# MotorDriverModule.net
KiCad netlist of a schematic drawn in EAGLE
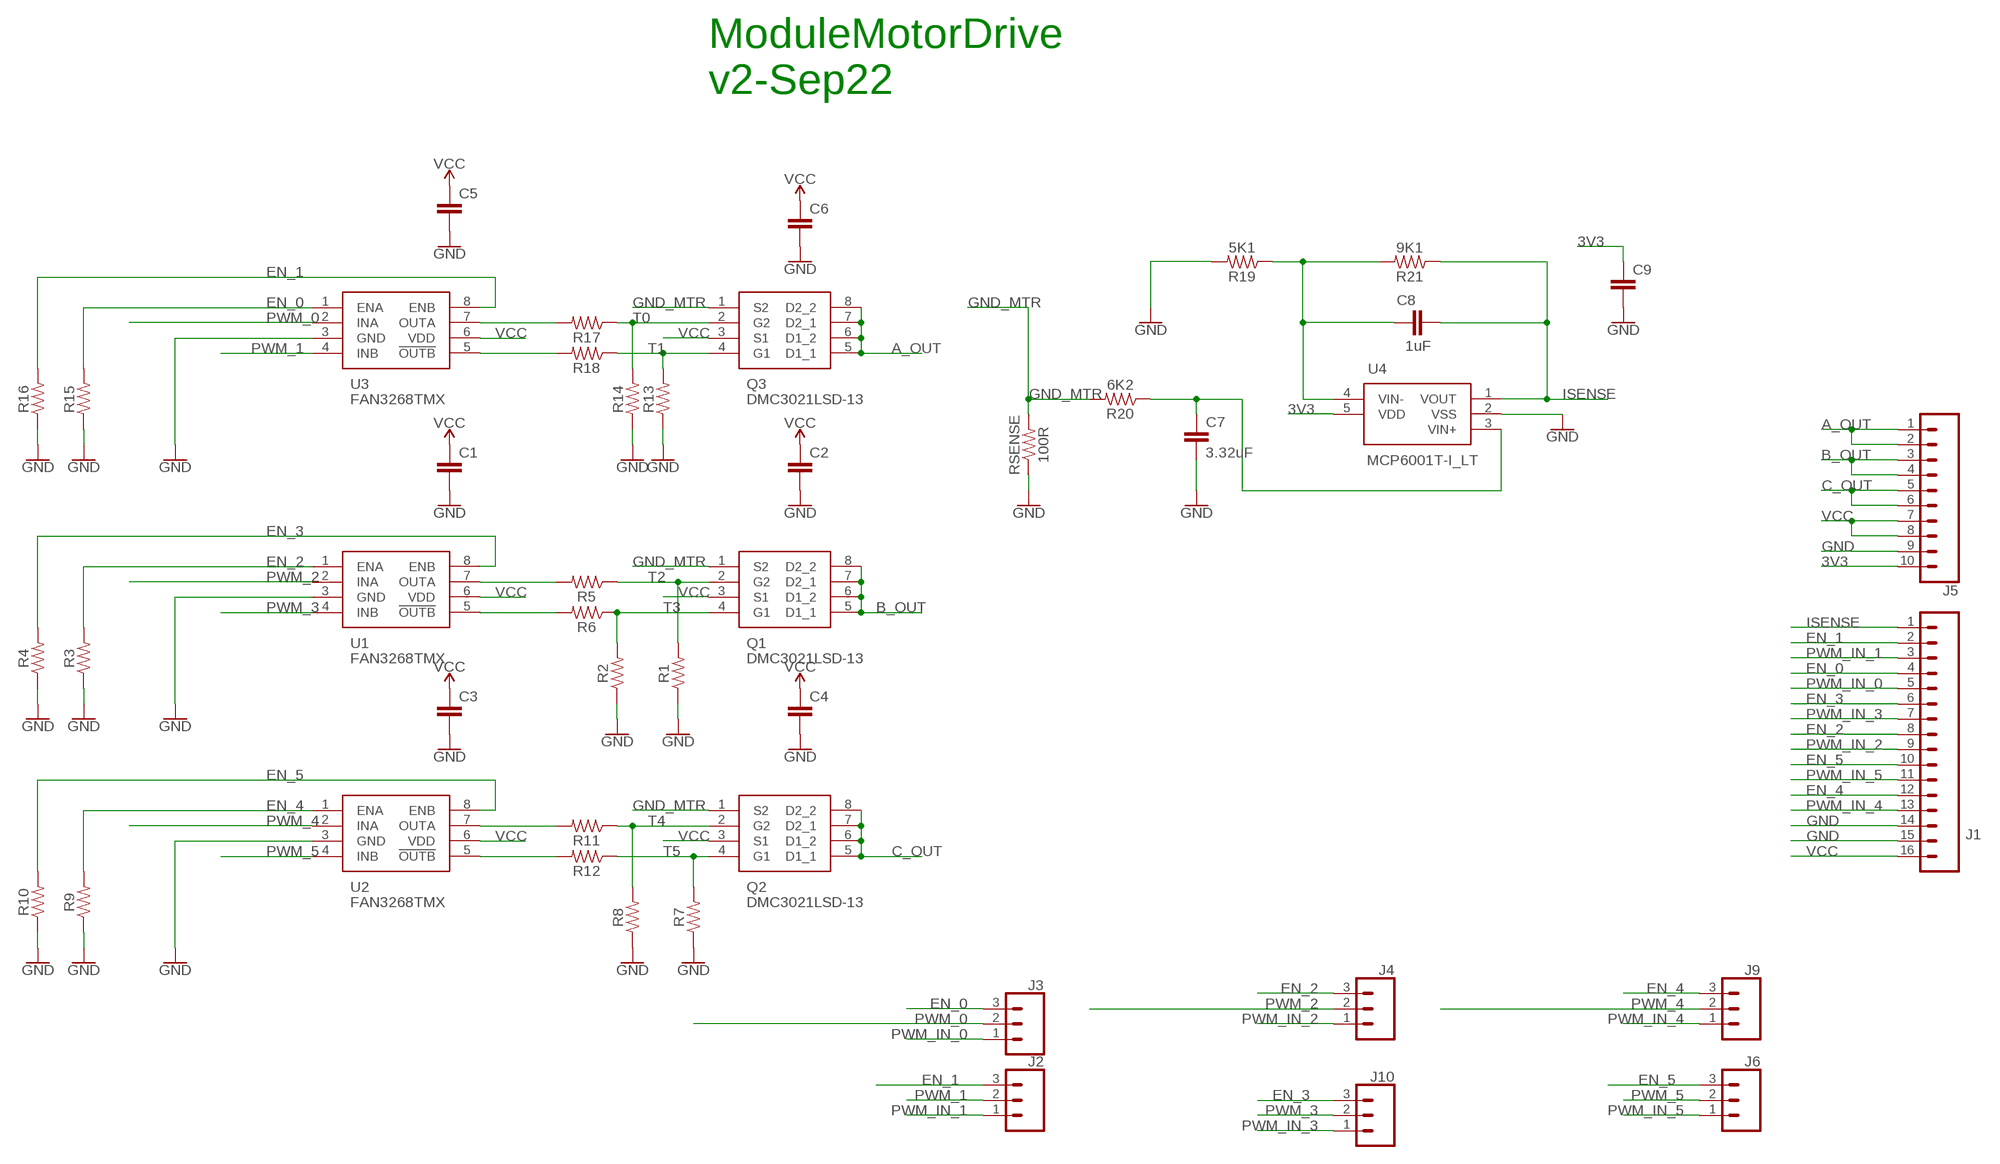
[diagram p0: schematic, sheet 1]

(export (version "E")
  (design (tool "Eeschema 10.0.6"))
  (components
    (comp (ref "C1")
      (value "C-EUC0805")
      (footprint "eagle-import:C0805")
      (libsource (lib "eagle-import") (part "C-EUC0805"))
    )
    (comp (ref "C2")
      (value "C-EUC0805")
      (footprint "eagle-import:C0805")
      (libsource (lib "eagle-import") (part "C-EUC0805"))
    )
    (comp (ref "C3")
      (value "C-EUC0805")
      (footprint "eagle-import:C0805")
      (libsource (lib "eagle-import") (part "C-EUC0805"))
    )
    (comp (ref "C4")
      (value "C-EUC0805")
      (footprint "eagle-import:C0805")
      (libsource (lib "eagle-import") (part "C-EUC0805"))
    )
    (comp (ref "C5")
      (value "C-EUC0805")
      (footprint "eagle-import:C0805")
      (libsource (lib "eagle-import") (part "C-EUC0805"))
    )
    (comp (ref "C6")
      (value "C-EUC0805")
      (footprint "eagle-import:C0805")
      (libsource (lib "eagle-import") (part "C-EUC0805"))
    )
    (comp (ref "C7")
      (value "3.32uF")
      (footprint "eagle-import:C0805")
      (libsource (lib "eagle-import") (part "C-EUC0805"))
    )
    (comp (ref "C8")
      (value "1uF")
      (footprint "eagle-import:C0805")
      (libsource (lib "eagle-import") (part "C-EUC0805"))
    )
    (comp (ref "C9")
      (value "C-EUC0805")
      (footprint "eagle-import:C0805")
      (libsource (lib "eagle-import") (part "C-EUC0805"))
    )
    (comp (ref "J1")
      (value "CONN_16")
      (footprint "eagle-import:1X16")
      (libsource (lib "eagle-import") (part "CONN_16"))
    )
    (comp (ref "J2")
      (value "CONN_03")
      (footprint "eagle-import:1X03")
      (libsource (lib "eagle-import") (part "CONN_03"))
    )
    (comp (ref "J3")
      (value "CONN_03")
      (footprint "eagle-import:1X03")
      (libsource (lib "eagle-import") (part "CONN_03"))
    )
    (comp (ref "J4")
      (value "CONN_03")
      (footprint "eagle-import:1X03")
      (libsource (lib "eagle-import") (part "CONN_03"))
    )
    (comp (ref "J5")
      (value "CONN_10\"")
      (footprint "eagle-import:1X10")
      (libsource (lib "eagle-import") (part "CONN_10{dblquote}"))
    )
    (comp (ref "J6")
      (value "CONN_03")
      (footprint "eagle-import:1X03")
      (libsource (lib "eagle-import") (part "CONN_03"))
    )
    (comp (ref "J9")
      (value "CONN_03")
      (footprint "eagle-import:1X03")
      (libsource (lib "eagle-import") (part "CONN_03"))
    )
    (comp (ref "J10")
      (value "CONN_03")
      (footprint "eagle-import:1X03")
      (libsource (lib "eagle-import") (part "CONN_03"))
    )
    (comp (ref "Q1")
      (value "DMC3021LSD-13")
      (footprint "eagle-import:SOIC127P600X175-8N")
      (fields (field (name "MOUSER_PART_NUMBER") "621-DMC3021LSD-13"))
      (libsource (lib "eagle-import") (part "DMC3021LSD-13"))
    )
    (comp (ref "Q2")
      (value "DMC3021LSD-13")
      (footprint "eagle-import:SOIC127P600X175-8N")
      (fields (field (name "MOUSER_PART_NUMBER") "621-DMC3021LSD-13"))
      (libsource (lib "eagle-import") (part "DMC3021LSD-13"))
    )
    (comp (ref "Q3")
      (value "DMC3021LSD-13")
      (footprint "eagle-import:SOIC127P600X175-8N")
      (fields (field (name "MOUSER_PART_NUMBER") "621-DMC3021LSD-13"))
      (libsource (lib "eagle-import") (part "DMC3021LSD-13"))
    )
    (comp (ref "R1")
      (value "RESISTOR0805")
      (footprint "eagle-import:0805")
      (libsource (lib "eagle-import") (part "RESISTOR0805"))
    )
    (comp (ref "R2")
      (value "RESISTOR0805")
      (footprint "eagle-import:0805")
      (libsource (lib "eagle-import") (part "RESISTOR0805"))
    )
    (comp (ref "R3")
      (value "RESISTOR0805")
      (footprint "eagle-import:0805")
      (libsource (lib "eagle-import") (part "RESISTOR0805"))
    )
    (comp (ref "R4")
      (value "RESISTOR0805")
      (footprint "eagle-import:0805")
      (libsource (lib "eagle-import") (part "RESISTOR0805"))
    )
    (comp (ref "R5")
      (value "RESISTOR0805")
      (footprint "eagle-import:0805")
      (libsource (lib "eagle-import") (part "RESISTOR0805"))
    )
    (comp (ref "R6")
      (value "RESISTOR0805")
      (footprint "eagle-import:0805")
      (libsource (lib "eagle-import") (part "RESISTOR0805"))
    )
    (comp (ref "R7")
      (value "RESISTOR0805")
      (footprint "eagle-import:0805")
      (libsource (lib "eagle-import") (part "RESISTOR0805"))
    )
    (comp (ref "R8")
      (value "RESISTOR0805")
      (footprint "eagle-import:0805")
      (libsource (lib "eagle-import") (part "RESISTOR0805"))
    )
    (comp (ref "R9")
      (value "RESISTOR0805")
      (footprint "eagle-import:0805")
      (libsource (lib "eagle-import") (part "RESISTOR0805"))
    )
    (comp (ref "R10")
      (value "RESISTOR0805")
      (footprint "eagle-import:0805")
      (libsource (lib "eagle-import") (part "RESISTOR0805"))
    )
    (comp (ref "R11")
      (value "RESISTOR0805")
      (footprint "eagle-import:0805")
      (libsource (lib "eagle-import") (part "RESISTOR0805"))
    )
    (comp (ref "R12")
      (value "RESISTOR0805")
      (footprint "eagle-import:0805")
      (libsource (lib "eagle-import") (part "RESISTOR0805"))
    )
    (comp (ref "R13")
      (value "RESISTOR0805")
      (footprint "eagle-import:0805")
      (libsource (lib "eagle-import") (part "RESISTOR0805"))
    )
    (comp (ref "R14")
      (value "RESISTOR0805")
      (footprint "eagle-import:0805")
      (libsource (lib "eagle-import") (part "RESISTOR0805"))
    )
    (comp (ref "R15")
      (value "RESISTOR0805")
      (footprint "eagle-import:0805")
      (libsource (lib "eagle-import") (part "RESISTOR0805"))
    )
    (comp (ref "R16")
      (value "RESISTOR0805")
      (footprint "eagle-import:0805")
      (libsource (lib "eagle-import") (part "RESISTOR0805"))
    )
    (comp (ref "R17")
      (value "RESISTOR0805")
      (footprint "eagle-import:0805")
      (libsource (lib "eagle-import") (part "RESISTOR0805"))
    )
    (comp (ref "R18")
      (value "RESISTOR0805")
      (footprint "eagle-import:0805")
      (libsource (lib "eagle-import") (part "RESISTOR0805"))
    )
    (comp (ref "R19")
      (value "5K1")
      (footprint "eagle-import:0805")
      (libsource (lib "eagle-import") (part "RESISTOR0805"))
    )
    (comp (ref "R20")
      (value "6K2")
      (footprint "eagle-import:0805")
      (libsource (lib "eagle-import") (part "RESISTOR0805"))
    )
    (comp (ref "R21")
      (value "9K1")
      (footprint "eagle-import:0805")
      (libsource (lib "eagle-import") (part "RESISTOR0805"))
    )
    (comp (ref "RSENSE")
      (value "100R")
      (footprint "eagle-import:1206")
      (libsource (lib "eagle-import") (part "RESISTOR1206"))
    )
    (comp (ref "U1")
      (value "FAN3268TMX")
      (footprint "eagle-import:SOIC127P600X175-8N")
      (fields (field (name "MOUSER_PART_NUMBER") "512-FAN3268TMX"))
      (libsource (lib "eagle-import") (part "FAN3268TMX"))
    )
    (comp (ref "U2")
      (value "FAN3268TMX")
      (footprint "eagle-import:SOIC127P600X175-8N")
      (fields (field (name "MOUSER_PART_NUMBER") "512-FAN3268TMX"))
      (libsource (lib "eagle-import") (part "FAN3268TMX"))
    )
    (comp (ref "U3")
      (value "FAN3268TMX")
      (footprint "eagle-import:SOIC127P600X175-8N")
      (fields (field (name "MOUSER_PART_NUMBER") "512-FAN3268TMX"))
      (libsource (lib "eagle-import") (part "FAN3268TMX"))
    )
    (comp (ref "U4")
      (value "MCP6001T-I_LT")
      (footprint "eagle-import:SOT65P210X110-5N")
      (fields
        (field (name "ARROW_PART_NUMBER") "MCP6001T-I/LT")
        (field (name "MOUSER_PART_NUMBER") "579-MCP6001T-I/LT")
      )
      (libsource (lib "eagle-import") (part "MCP6001T-I_LT"))
    )
  )
  (nets
    (net (code "1") (name "/3V3") (class "Default")
      (node (ref "C9") (pin "1") (pinfunction "1_1") (pintype "passive"))
      (node (ref "J5") (pin "10") (pinfunction "10_10") (pintype "passive"))
      (node (ref "U4") (pin "5") (pinfunction "VDD_5") (pintype "bidirectional"))
    )
    (net (code "2") (name "/A_OUT") (class "Default")
      (node (ref "J5") (pin "1") (pinfunction "1_1") (pintype "passive"))
      (node (ref "J5") (pin "2") (pinfunction "2_2") (pintype "passive"))
      (node (ref "Q3") (pin "5") (pinfunction "D1_1_5") (pintype "bidirectional"))
      (node (ref "Q3") (pin "6") (pinfunction "D1_2_6") (pintype "bidirectional"))
      (node (ref "Q3") (pin "7") (pinfunction "D2_1_7") (pintype "bidirectional"))
      (node (ref "Q3") (pin "8") (pinfunction "D2_2_8") (pintype "bidirectional"))
    )
    (net (code "3") (name "/B_OUT") (class "Default")
      (node (ref "J5") (pin "3") (pinfunction "3_3") (pintype "passive"))
      (node (ref "J5") (pin "4") (pinfunction "4_4") (pintype "passive"))
      (node (ref "Q1") (pin "5") (pinfunction "D1_1_5") (pintype "bidirectional"))
      (node (ref "Q1") (pin "6") (pinfunction "D1_2_6") (pintype "bidirectional"))
      (node (ref "Q1") (pin "7") (pinfunction "D2_1_7") (pintype "bidirectional"))
      (node (ref "Q1") (pin "8") (pinfunction "D2_2_8") (pintype "bidirectional"))
    )
    (net (code "4") (name "/C_OUT") (class "Default")
      (node (ref "J5") (pin "5") (pinfunction "5_5") (pintype "passive"))
      (node (ref "J5") (pin "6") (pinfunction "6_6") (pintype "passive"))
      (node (ref "Q2") (pin "5") (pinfunction "D1_1_5") (pintype "bidirectional"))
      (node (ref "Q2") (pin "6") (pinfunction "D1_2_6") (pintype "bidirectional"))
      (node (ref "Q2") (pin "7") (pinfunction "D2_1_7") (pintype "bidirectional"))
      (node (ref "Q2") (pin "8") (pinfunction "D2_2_8") (pintype "bidirectional"))
    )
    (net (code "5") (name "/EN_0") (class "Default")
      (node (ref "J1") (pin "4") (pinfunction "4_4") (pintype "passive"))
      (node (ref "J3") (pin "3") (pinfunction "3_3") (pintype "passive"))
      (node (ref "R15") (pin "2") (pinfunction "2_2") (pintype "passive"))
      (node (ref "U3") (pin "1") (pinfunction "ENA_1") (pintype "bidirectional"))
    )
    (net (code "6") (name "/EN_1") (class "Default")
      (node (ref "J1") (pin "2") (pinfunction "2_2") (pintype "passive"))
      (node (ref "J2") (pin "3") (pinfunction "3_3") (pintype "passive"))
      (node (ref "R16") (pin "2") (pinfunction "2_2") (pintype "passive"))
      (node (ref "U3") (pin "8") (pinfunction "ENB_8") (pintype "bidirectional"))
    )
    (net (code "7") (name "/EN_2") (class "Default")
      (node (ref "J1") (pin "8") (pinfunction "8_8") (pintype "passive"))
      (node (ref "J4") (pin "3") (pinfunction "3_3") (pintype "passive"))
      (node (ref "R3") (pin "2") (pinfunction "2_2") (pintype "passive"))
      (node (ref "U1") (pin "1") (pinfunction "ENA_1") (pintype "bidirectional"))
    )
    (net (code "8") (name "/EN_3") (class "Default")
      (node (ref "J1") (pin "6") (pinfunction "6_6") (pintype "passive"))
      (node (ref "J10") (pin "3") (pinfunction "3_3") (pintype "passive"))
      (node (ref "R4") (pin "2") (pinfunction "2_2") (pintype "passive"))
      (node (ref "U1") (pin "8") (pinfunction "ENB_8") (pintype "bidirectional"))
    )
    (net (code "9") (name "/EN_4") (class "Default")
      (node (ref "J1") (pin "12") (pinfunction "12_12") (pintype "passive"))
      (node (ref "J9") (pin "3") (pinfunction "3_3") (pintype "passive"))
      (node (ref "R9") (pin "2") (pinfunction "2_2") (pintype "passive"))
      (node (ref "U2") (pin "1") (pinfunction "ENA_1") (pintype "bidirectional"))
    )
    (net (code "10") (name "/EN_5") (class "Default")
      (node (ref "J1") (pin "10") (pinfunction "10_10") (pintype "passive"))
      (node (ref "J6") (pin "3") (pinfunction "3_3") (pintype "passive"))
      (node (ref "R10") (pin "2") (pinfunction "2_2") (pintype "passive"))
      (node (ref "U2") (pin "8") (pinfunction "ENB_8") (pintype "bidirectional"))
    )
    (net (code "11") (name "/GND_MTR") (class "Default")
      (node (ref "Q1") (pin "1") (pinfunction "S2_1") (pintype "bidirectional"))
      (node (ref "Q2") (pin "1") (pinfunction "S2_1") (pintype "bidirectional"))
      (node (ref "Q3") (pin "1") (pinfunction "S2_1") (pintype "bidirectional"))
      (node (ref "R20") (pin "2") (pinfunction "2_2") (pintype "passive"))
      (node (ref "RSENSE") (pin "2") (pinfunction "2_2") (pintype "passive"))
    )
    (net (code "12") (name "/ISENSE") (class "Default")
      (node (ref "C8") (pin "2") (pinfunction "2_2") (pintype "passive"))
      (node (ref "J1") (pin "1") (pinfunction "1_1") (pintype "passive"))
      (node (ref "R21") (pin "1") (pinfunction "1_1") (pintype "passive"))
      (node (ref "U4") (pin "1") (pinfunction "VOUT_1") (pintype "bidirectional"))
    )
    (net (code "13") (name "/PWM_0") (class "Default")
      (node (ref "J3") (pin "2") (pinfunction "2_2") (pintype "passive"))
      (node (ref "U3") (pin "2") (pinfunction "INA_2") (pintype "bidirectional"))
    )
    (net (code "14") (name "/PWM_1") (class "Default")
      (node (ref "J2") (pin "2") (pinfunction "2_2") (pintype "passive"))
      (node (ref "U3") (pin "4") (pinfunction "INB_4") (pintype "bidirectional"))
    )
    (net (code "15") (name "/PWM_2") (class "Default")
      (node (ref "J4") (pin "2") (pinfunction "2_2") (pintype "passive"))
      (node (ref "U1") (pin "2") (pinfunction "INA_2") (pintype "bidirectional"))
    )
    (net (code "16") (name "/PWM_3") (class "Default")
      (node (ref "J10") (pin "2") (pinfunction "2_2") (pintype "passive"))
      (node (ref "U1") (pin "4") (pinfunction "INB_4") (pintype "bidirectional"))
    )
    (net (code "17") (name "/PWM_4") (class "Default")
      (node (ref "J9") (pin "2") (pinfunction "2_2") (pintype "passive"))
      (node (ref "U2") (pin "2") (pinfunction "INA_2") (pintype "bidirectional"))
    )
    (net (code "18") (name "/PWM_5") (class "Default")
      (node (ref "J6") (pin "2") (pinfunction "2_2") (pintype "passive"))
      (node (ref "U2") (pin "4") (pinfunction "INB_4") (pintype "bidirectional"))
    )
    (net (code "19") (name "/PWM_IN_0") (class "Default")
      (node (ref "J1") (pin "5") (pinfunction "5_5") (pintype "passive"))
      (node (ref "J3") (pin "1") (pinfunction "1_1") (pintype "passive"))
    )
    (net (code "20") (name "/PWM_IN_1") (class "Default")
      (node (ref "J1") (pin "3") (pinfunction "3_3") (pintype "passive"))
      (node (ref "J2") (pin "1") (pinfunction "1_1") (pintype "passive"))
    )
    (net (code "21") (name "/PWM_IN_2") (class "Default")
      (node (ref "J1") (pin "9") (pinfunction "9_9") (pintype "passive"))
      (node (ref "J4") (pin "1") (pinfunction "1_1") (pintype "passive"))
    )
    (net (code "22") (name "/PWM_IN_3") (class "Default")
      (node (ref "J1") (pin "7") (pinfunction "7_7") (pintype "passive"))
      (node (ref "J10") (pin "1") (pinfunction "1_1") (pintype "passive"))
    )
    (net (code "23") (name "/PWM_IN_4") (class "Default")
      (node (ref "J1") (pin "13") (pinfunction "13_13") (pintype "passive"))
      (node (ref "J9") (pin "1") (pinfunction "1_1") (pintype "passive"))
    )
    (net (code "24") (name "/PWM_IN_5") (class "Default")
      (node (ref "J1") (pin "11") (pinfunction "11_11") (pintype "passive"))
      (node (ref "J6") (pin "1") (pinfunction "1_1") (pintype "passive"))
    )
    (net (code "25") (name "/T0") (class "Default")
      (node (ref "Q3") (pin "2") (pinfunction "G2_2") (pintype "bidirectional"))
      (node (ref "R14") (pin "2") (pinfunction "2_2") (pintype "passive"))
      (node (ref "R17") (pin "1") (pinfunction "1_1") (pintype "passive"))
    )
    (net (code "26") (name "/T1") (class "Default")
      (node (ref "Q3") (pin "4") (pinfunction "G1_4") (pintype "bidirectional"))
      (node (ref "R13") (pin "2") (pinfunction "2_2") (pintype "passive"))
      (node (ref "R18") (pin "1") (pinfunction "1_1") (pintype "passive"))
    )
    (net (code "27") (name "/T2") (class "Default")
      (node (ref "Q1") (pin "2") (pinfunction "G2_2") (pintype "bidirectional"))
      (node (ref "R1") (pin "2") (pinfunction "2_2") (pintype "passive"))
      (node (ref "R5") (pin "1") (pinfunction "1_1") (pintype "passive"))
    )
    (net (code "28") (name "/T3") (class "Default")
      (node (ref "Q1") (pin "4") (pinfunction "G1_4") (pintype "bidirectional"))
      (node (ref "R2") (pin "2") (pinfunction "2_2") (pintype "passive"))
      (node (ref "R6") (pin "1") (pinfunction "1_1") (pintype "passive"))
    )
    (net (code "29") (name "/T4") (class "Default")
      (node (ref "Q2") (pin "2") (pinfunction "G2_2") (pintype "bidirectional"))
      (node (ref "R11") (pin "1") (pinfunction "1_1") (pintype "passive"))
      (node (ref "R8") (pin "2") (pinfunction "2_2") (pintype "passive"))
    )
    (net (code "30") (name "/T5") (class "Default")
      (node (ref "Q2") (pin "4") (pinfunction "G1_4") (pintype "bidirectional"))
      (node (ref "R12") (pin "1") (pinfunction "1_1") (pintype "passive"))
      (node (ref "R7") (pin "2") (pinfunction "2_2") (pintype "passive"))
    )
    (net (code "31") (name "GND") (class "Default")
      (node (ref "C1") (pin "2") (pinfunction "2_2") (pintype "passive"))
      (node (ref "C2") (pin "2") (pinfunction "2_2") (pintype "passive"))
      (node (ref "C3") (pin "2") (pinfunction "2_2") (pintype "passive"))
      (node (ref "C4") (pin "2") (pinfunction "2_2") (pintype "passive"))
      (node (ref "C5") (pin "2") (pinfunction "2_2") (pintype "passive"))
      (node (ref "C6") (pin "2") (pinfunction "2_2") (pintype "passive"))
      (node (ref "C7") (pin "2") (pinfunction "2_2") (pintype "passive"))
      (node (ref "C9") (pin "2") (pinfunction "2_2") (pintype "passive"))
      (node (ref "J1") (pin "14") (pinfunction "14_14") (pintype "passive"))
      (node (ref "J1") (pin "15") (pinfunction "15_15") (pintype "passive"))
      (node (ref "J5") (pin "9") (pinfunction "9_9") (pintype "passive"))
      (node (ref "R1") (pin "1") (pinfunction "1_1") (pintype "passive"))
      (node (ref "R10") (pin "1") (pinfunction "1_1") (pintype "passive"))
      (node (ref "R13") (pin "1") (pinfunction "1_1") (pintype "passive"))
      (node (ref "R14") (pin "1") (pinfunction "1_1") (pintype "passive"))
      (node (ref "R15") (pin "1") (pinfunction "1_1") (pintype "passive"))
      (node (ref "R16") (pin "1") (pinfunction "1_1") (pintype "passive"))
      (node (ref "R19") (pin "2") (pinfunction "2_2") (pintype "passive"))
      (node (ref "R2") (pin "1") (pinfunction "1_1") (pintype "passive"))
      (node (ref "R3") (pin "1") (pinfunction "1_1") (pintype "passive"))
      (node (ref "R4") (pin "1") (pinfunction "1_1") (pintype "passive"))
      (node (ref "R7") (pin "1") (pinfunction "1_1") (pintype "passive"))
      (node (ref "R8") (pin "1") (pinfunction "1_1") (pintype "passive"))
      (node (ref "R9") (pin "1") (pinfunction "1_1") (pintype "passive"))
      (node (ref "RSENSE") (pin "1") (pinfunction "1_1") (pintype "passive"))
      (node (ref "U1") (pin "3") (pinfunction "GND_3") (pintype "bidirectional"))
      (node (ref "U2") (pin "3") (pinfunction "GND_3") (pintype "bidirectional"))
      (node (ref "U3") (pin "3") (pinfunction "GND_3") (pintype "bidirectional"))
      (node (ref "U4") (pin "2") (pinfunction "VSS_2") (pintype "bidirectional"))
    )
    (net (code "32") (name "Net-(U1-OUTA)") (class "Default")
      (node (ref "R5") (pin "2") (pinfunction "2_2") (pintype "passive"))
      (node (ref "U1") (pin "7") (pinfunction "OUTA_7") (pintype "bidirectional"))
    )
    (net (code "33") (name "Net-(U1-~{OUTB})") (class "Default")
      (node (ref "R6") (pin "2") (pinfunction "2_2") (pintype "passive"))
      (node (ref "U1") (pin "5") (pinfunction "~{OUTB}_5") (pintype "bidirectional"))
    )
    (net (code "34") (name "Net-(U2-OUTA)") (class "Default")
      (node (ref "R11") (pin "2") (pinfunction "2_2") (pintype "passive"))
      (node (ref "U2") (pin "7") (pinfunction "OUTA_7") (pintype "bidirectional"))
    )
    (net (code "35") (name "Net-(U2-~{OUTB})") (class "Default")
      (node (ref "R12") (pin "2") (pinfunction "2_2") (pintype "passive"))
      (node (ref "U2") (pin "5") (pinfunction "~{OUTB}_5") (pintype "bidirectional"))
    )
    (net (code "36") (name "Net-(U3-OUTA)") (class "Default")
      (node (ref "R17") (pin "2") (pinfunction "2_2") (pintype "passive"))
      (node (ref "U3") (pin "7") (pinfunction "OUTA_7") (pintype "bidirectional"))
    )
    (net (code "37") (name "Net-(U3-~{OUTB})") (class "Default")
      (node (ref "R18") (pin "2") (pinfunction "2_2") (pintype "passive"))
      (node (ref "U3") (pin "5") (pinfunction "~{OUTB}_5") (pintype "bidirectional"))
    )
    (net (code "38") (name "Net-(U4-VIN+)") (class "Default")
      (node (ref "C7") (pin "1") (pinfunction "1_1") (pintype "passive"))
      (node (ref "R20") (pin "1") (pinfunction "1_1") (pintype "passive"))
      (node (ref "U4") (pin "3") (pinfunction "VIN+_3") (pintype "bidirectional"))
    )
    (net (code "39") (name "Net-(U4-VIN-)") (class "Default")
      (node (ref "C8") (pin "1") (pinfunction "1_1") (pintype "passive"))
      (node (ref "R19") (pin "1") (pinfunction "1_1") (pintype "passive"))
      (node (ref "R21") (pin "2") (pinfunction "2_2") (pintype "passive"))
      (node (ref "U4") (pin "4") (pinfunction "VIN-_4") (pintype "bidirectional"))
    )
    (net (code "40") (name "VCC") (class "Default")
      (node (ref "C1") (pin "1") (pinfunction "1_1") (pintype "passive"))
      (node (ref "C2") (pin "1") (pinfunction "1_1") (pintype "passive"))
      (node (ref "C3") (pin "1") (pinfunction "1_1") (pintype "passive"))
      (node (ref "C4") (pin "1") (pinfunction "1_1") (pintype "passive"))
      (node (ref "C5") (pin "1") (pinfunction "1_1") (pintype "passive"))
      (node (ref "C6") (pin "1") (pinfunction "1_1") (pintype "passive"))
      (node (ref "J1") (pin "16") (pinfunction "16_16") (pintype "passive"))
      (node (ref "J5") (pin "7") (pinfunction "7_7") (pintype "passive"))
      (node (ref "J5") (pin "8") (pinfunction "8_8") (pintype "passive"))
      (node (ref "Q1") (pin "3") (pinfunction "S1_3") (pintype "bidirectional"))
      (node (ref "Q2") (pin "3") (pinfunction "S1_3") (pintype "bidirectional"))
      (node (ref "Q3") (pin "3") (pinfunction "S1_3") (pintype "bidirectional"))
      (node (ref "U1") (pin "6") (pinfunction "VDD_6") (pintype "bidirectional"))
      (node (ref "U2") (pin "6") (pinfunction "VDD_6") (pintype "bidirectional"))
      (node (ref "U3") (pin "6") (pinfunction "VDD_6") (pintype "bidirectional"))
    )
  )
)
